# FLD_Logic_2.net
KiCad netlist of a schematic drawn in EAGLE
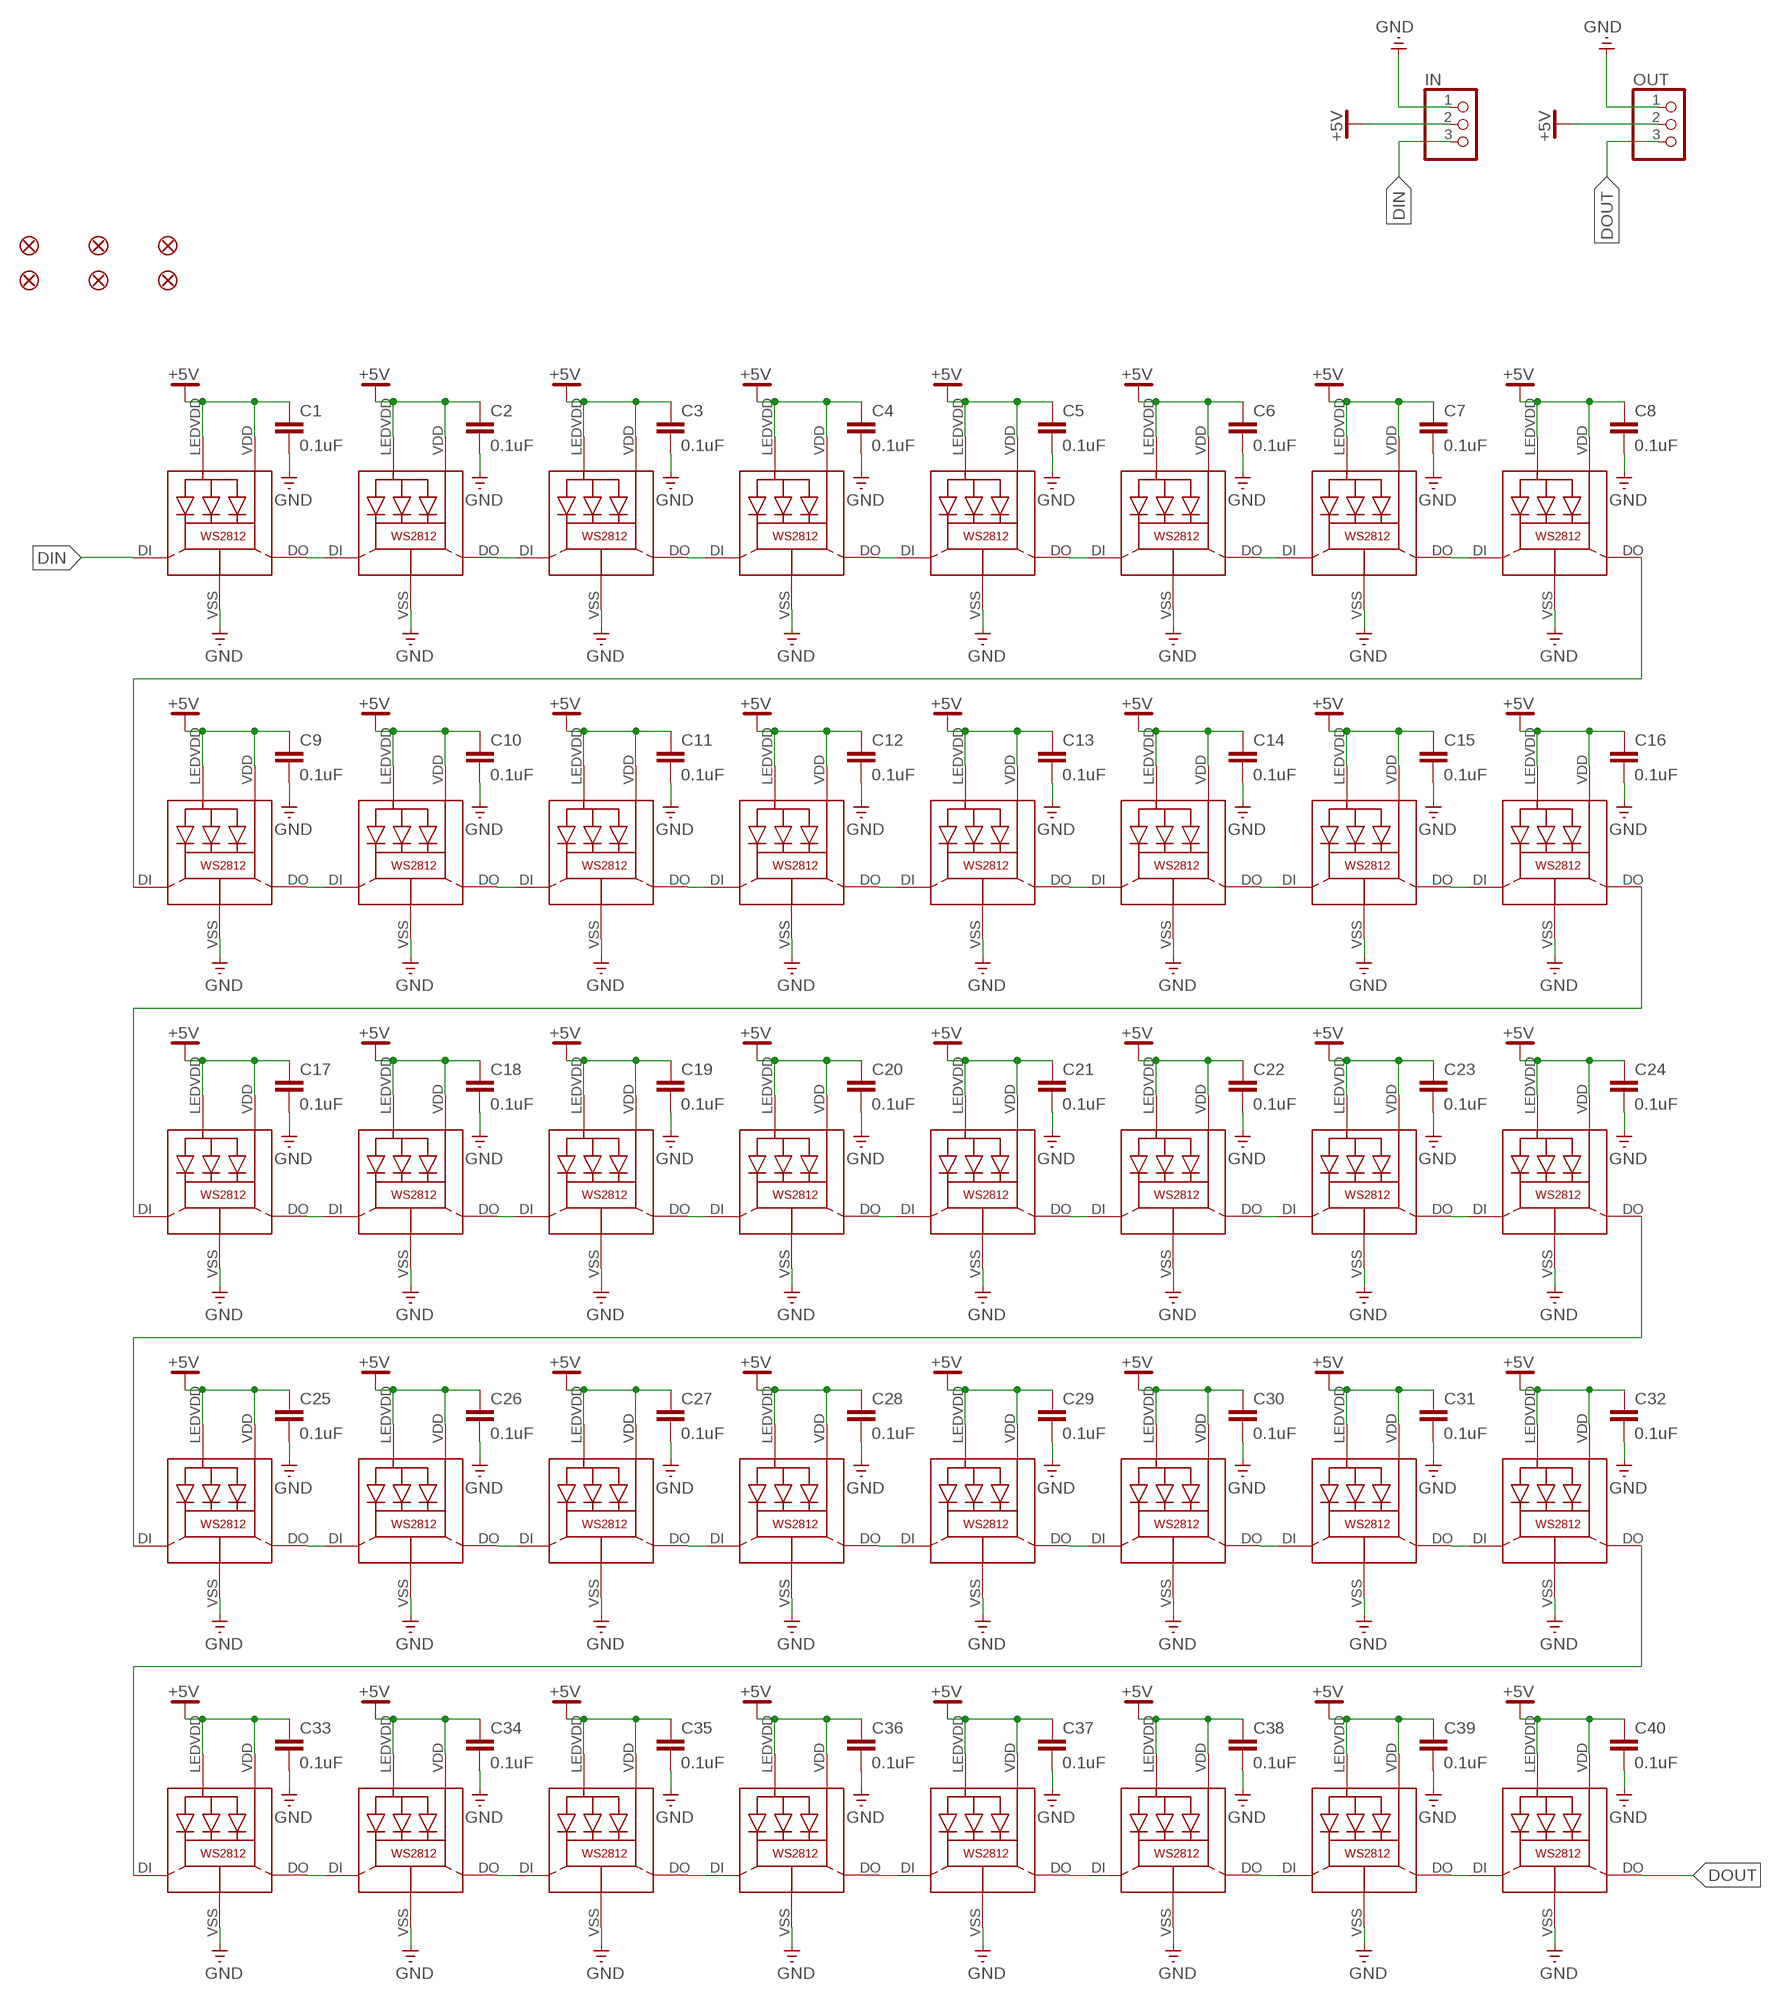
[diagram p0: schematic, sheet 1]

(export (version "E")
  (design (tool "Eeschema 10.0.6"))
  (components
    (comp (ref "C1")
      (value "0.1uF")
      (footprint "eagle-import:0805")
      (libsource (lib "eagle-import") (part "CAP0805"))
    )
    (comp (ref "C2")
      (value "0.1uF")
      (footprint "eagle-import:0805")
      (libsource (lib "eagle-import") (part "CAP0805"))
    )
    (comp (ref "C3")
      (value "0.1uF")
      (footprint "eagle-import:0805")
      (libsource (lib "eagle-import") (part "CAP0805"))
    )
    (comp (ref "C4")
      (value "0.1uF")
      (footprint "eagle-import:0805")
      (libsource (lib "eagle-import") (part "CAP0805"))
    )
    (comp (ref "C5")
      (value "0.1uF")
      (footprint "eagle-import:0805")
      (libsource (lib "eagle-import") (part "CAP0805"))
    )
    (comp (ref "C6")
      (value "0.1uF")
      (footprint "eagle-import:0805")
      (libsource (lib "eagle-import") (part "CAP0805"))
    )
    (comp (ref "C7")
      (value "0.1uF")
      (footprint "eagle-import:0805")
      (libsource (lib "eagle-import") (part "CAP0805"))
    )
    (comp (ref "C8")
      (value "0.1uF")
      (footprint "eagle-import:0805")
      (libsource (lib "eagle-import") (part "CAP0805"))
    )
    (comp (ref "C9")
      (value "0.1uF")
      (footprint "eagle-import:0805")
      (libsource (lib "eagle-import") (part "CAP0805"))
    )
    (comp (ref "C10")
      (value "0.1uF")
      (footprint "eagle-import:0805")
      (libsource (lib "eagle-import") (part "CAP0805"))
    )
    (comp (ref "C11")
      (value "0.1uF")
      (footprint "eagle-import:0805")
      (libsource (lib "eagle-import") (part "CAP0805"))
    )
    (comp (ref "C12")
      (value "0.1uF")
      (footprint "eagle-import:0805")
      (libsource (lib "eagle-import") (part "CAP0805"))
    )
    (comp (ref "C13")
      (value "0.1uF")
      (footprint "eagle-import:0805")
      (libsource (lib "eagle-import") (part "CAP0805"))
    )
    (comp (ref "C14")
      (value "0.1uF")
      (footprint "eagle-import:0805")
      (libsource (lib "eagle-import") (part "CAP0805"))
    )
    (comp (ref "C15")
      (value "0.1uF")
      (footprint "eagle-import:0805")
      (libsource (lib "eagle-import") (part "CAP0805"))
    )
    (comp (ref "C16")
      (value "0.1uF")
      (footprint "eagle-import:0805")
      (libsource (lib "eagle-import") (part "CAP0805"))
    )
    (comp (ref "C17")
      (value "0.1uF")
      (footprint "eagle-import:0805")
      (libsource (lib "eagle-import") (part "CAP0805"))
    )
    (comp (ref "C18")
      (value "0.1uF")
      (footprint "eagle-import:0805")
      (libsource (lib "eagle-import") (part "CAP0805"))
    )
    (comp (ref "C19")
      (value "0.1uF")
      (footprint "eagle-import:0805")
      (libsource (lib "eagle-import") (part "CAP0805"))
    )
    (comp (ref "C20")
      (value "0.1uF")
      (footprint "eagle-import:0805")
      (libsource (lib "eagle-import") (part "CAP0805"))
    )
    (comp (ref "C21")
      (value "0.1uF")
      (footprint "eagle-import:0805")
      (libsource (lib "eagle-import") (part "CAP0805"))
    )
    (comp (ref "C22")
      (value "0.1uF")
      (footprint "eagle-import:0805")
      (libsource (lib "eagle-import") (part "CAP0805"))
    )
    (comp (ref "C23")
      (value "0.1uF")
      (footprint "eagle-import:0805")
      (libsource (lib "eagle-import") (part "CAP0805"))
    )
    (comp (ref "C24")
      (value "0.1uF")
      (footprint "eagle-import:0805")
      (libsource (lib "eagle-import") (part "CAP0805"))
    )
    (comp (ref "C25")
      (value "0.1uF")
      (footprint "eagle-import:0805")
      (libsource (lib "eagle-import") (part "CAP0805"))
    )
    (comp (ref "C26")
      (value "0.1uF")
      (footprint "eagle-import:0805")
      (libsource (lib "eagle-import") (part "CAP0805"))
    )
    (comp (ref "C27")
      (value "0.1uF")
      (footprint "eagle-import:0805")
      (libsource (lib "eagle-import") (part "CAP0805"))
    )
    (comp (ref "C28")
      (value "0.1uF")
      (footprint "eagle-import:0805")
      (libsource (lib "eagle-import") (part "CAP0805"))
    )
    (comp (ref "C29")
      (value "0.1uF")
      (footprint "eagle-import:0805")
      (libsource (lib "eagle-import") (part "CAP0805"))
    )
    (comp (ref "C30")
      (value "0.1uF")
      (footprint "eagle-import:0805")
      (libsource (lib "eagle-import") (part "CAP0805"))
    )
    (comp (ref "C31")
      (value "0.1uF")
      (footprint "eagle-import:0805")
      (libsource (lib "eagle-import") (part "CAP0805"))
    )
    (comp (ref "C32")
      (value "0.1uF")
      (footprint "eagle-import:0805")
      (libsource (lib "eagle-import") (part "CAP0805"))
    )
    (comp (ref "C33")
      (value "0.1uF")
      (footprint "eagle-import:0805")
      (libsource (lib "eagle-import") (part "CAP0805"))
    )
    (comp (ref "C34")
      (value "0.1uF")
      (footprint "eagle-import:0805")
      (libsource (lib "eagle-import") (part "CAP0805"))
    )
    (comp (ref "C35")
      (value "0.1uF")
      (footprint "eagle-import:0805")
      (libsource (lib "eagle-import") (part "CAP0805"))
    )
    (comp (ref "C36")
      (value "0.1uF")
      (footprint "eagle-import:0805")
      (libsource (lib "eagle-import") (part "CAP0805"))
    )
    (comp (ref "C37")
      (value "0.1uF")
      (footprint "eagle-import:0805")
      (libsource (lib "eagle-import") (part "CAP0805"))
    )
    (comp (ref "C38")
      (value "0.1uF")
      (footprint "eagle-import:0805")
      (libsource (lib "eagle-import") (part "CAP0805"))
    )
    (comp (ref "C39")
      (value "0.1uF")
      (footprint "eagle-import:0805")
      (libsource (lib "eagle-import") (part "CAP0805"))
    )
    (comp (ref "C40")
      (value "0.1uF")
      (footprint "eagle-import:0805")
      (libsource (lib "eagle-import") (part "CAP0805"))
    )
    (comp (ref "FID1")
      (value "FIDUCIAL1.5X3")
      (footprint "eagle-import:FIDUCIAL-1.5X3")
      (libsource (lib "eagle-import") (part "FIDUCIAL1.5X3"))
    )
    (comp (ref "FID2")
      (value "FIDUCIAL1.5X3")
      (footprint "eagle-import:FIDUCIAL-1.5X3")
      (libsource (lib "eagle-import") (part "FIDUCIAL1.5X3"))
    )
    (comp (ref "FID3")
      (value "FIDUCIAL1.5X3")
      (footprint "eagle-import:FIDUCIAL-1.5X3")
      (libsource (lib "eagle-import") (part "FIDUCIAL1.5X3"))
    )
    (comp (ref "FID4")
      (value "FIDUCIAL1.5X3")
      (footprint "eagle-import:FIDUCIAL-1.5X3")
      (libsource (lib "eagle-import") (part "FIDUCIAL1.5X3"))
    )
    (comp (ref "FID5")
      (value "FIDUCIAL1.5X3")
      (footprint "eagle-import:FIDUCIAL-1.5X3")
      (libsource (lib "eagle-import") (part "FIDUCIAL1.5X3"))
    )
    (comp (ref "FID6")
      (value "FIDUCIAL1.5X3")
      (footprint "eagle-import:FIDUCIAL-1.5X3")
      (libsource (lib "eagle-import") (part "FIDUCIAL1.5X3"))
    )
    (comp (ref "IN")
      (value "PINHD-1X3")
      (footprint "eagle-import:1X03")
      (libsource (lib "eagle-import") (part "PINHD-1X3"))
    )
    (comp (ref "LED1")
      (value "WS2812")
      (footprint "eagle-import:WS2812")
      (libsource (lib "eagle-import") (part "WS2812"))
    )
    (comp (ref "LED2")
      (value "WS2812")
      (footprint "eagle-import:WS2812")
      (libsource (lib "eagle-import") (part "WS2812"))
    )
    (comp (ref "LED3")
      (value "WS2812")
      (footprint "eagle-import:WS2812")
      (libsource (lib "eagle-import") (part "WS2812"))
    )
    (comp (ref "LED4")
      (value "WS2812")
      (footprint "eagle-import:WS2812")
      (libsource (lib "eagle-import") (part "WS2812"))
    )
    (comp (ref "LED5")
      (value "WS2812")
      (footprint "eagle-import:WS2812")
      (libsource (lib "eagle-import") (part "WS2812"))
    )
    (comp (ref "LED6")
      (value "WS2812")
      (footprint "eagle-import:WS2812")
      (libsource (lib "eagle-import") (part "WS2812"))
    )
    (comp (ref "LED7")
      (value "WS2812")
      (footprint "eagle-import:WS2812")
      (libsource (lib "eagle-import") (part "WS2812"))
    )
    (comp (ref "LED8")
      (value "WS2812")
      (footprint "eagle-import:WS2812")
      (libsource (lib "eagle-import") (part "WS2812"))
    )
    (comp (ref "LED9")
      (value "WS2812")
      (footprint "eagle-import:WS2812")
      (libsource (lib "eagle-import") (part "WS2812"))
    )
    (comp (ref "LED10")
      (value "WS2812")
      (footprint "eagle-import:WS2812")
      (libsource (lib "eagle-import") (part "WS2812"))
    )
    (comp (ref "LED11")
      (value "WS2812")
      (footprint "eagle-import:WS2812")
      (libsource (lib "eagle-import") (part "WS2812"))
    )
    (comp (ref "LED12")
      (value "WS2812")
      (footprint "eagle-import:WS2812")
      (libsource (lib "eagle-import") (part "WS2812"))
    )
    (comp (ref "LED13")
      (value "WS2812")
      (footprint "eagle-import:WS2812")
      (libsource (lib "eagle-import") (part "WS2812"))
    )
    (comp (ref "LED14")
      (value "WS2812")
      (footprint "eagle-import:WS2812")
      (libsource (lib "eagle-import") (part "WS2812"))
    )
    (comp (ref "LED15")
      (value "WS2812")
      (footprint "eagle-import:WS2812")
      (libsource (lib "eagle-import") (part "WS2812"))
    )
    (comp (ref "LED16")
      (value "WS2812")
      (footprint "eagle-import:WS2812")
      (libsource (lib "eagle-import") (part "WS2812"))
    )
    (comp (ref "LED17")
      (value "WS2812")
      (footprint "eagle-import:WS2812")
      (libsource (lib "eagle-import") (part "WS2812"))
    )
    (comp (ref "LED18")
      (value "WS2812")
      (footprint "eagle-import:WS2812")
      (libsource (lib "eagle-import") (part "WS2812"))
    )
    (comp (ref "LED19")
      (value "WS2812")
      (footprint "eagle-import:WS2812")
      (libsource (lib "eagle-import") (part "WS2812"))
    )
    (comp (ref "LED20")
      (value "WS2812")
      (footprint "eagle-import:WS2812")
      (libsource (lib "eagle-import") (part "WS2812"))
    )
    (comp (ref "LED21")
      (value "WS2812")
      (footprint "eagle-import:WS2812")
      (libsource (lib "eagle-import") (part "WS2812"))
    )
    (comp (ref "LED22")
      (value "WS2812")
      (footprint "eagle-import:WS2812")
      (libsource (lib "eagle-import") (part "WS2812"))
    )
    (comp (ref "LED23")
      (value "WS2812")
      (footprint "eagle-import:WS2812")
      (libsource (lib "eagle-import") (part "WS2812"))
    )
    (comp (ref "LED24")
      (value "WS2812")
      (footprint "eagle-import:WS2812")
      (libsource (lib "eagle-import") (part "WS2812"))
    )
    (comp (ref "LED25")
      (value "WS2812")
      (footprint "eagle-import:WS2812")
      (libsource (lib "eagle-import") (part "WS2812"))
    )
    (comp (ref "LED26")
      (value "WS2812")
      (footprint "eagle-import:WS2812")
      (libsource (lib "eagle-import") (part "WS2812"))
    )
    (comp (ref "LED27")
      (value "WS2812")
      (footprint "eagle-import:WS2812")
      (libsource (lib "eagle-import") (part "WS2812"))
    )
    (comp (ref "LED28")
      (value "WS2812")
      (footprint "eagle-import:WS2812")
      (libsource (lib "eagle-import") (part "WS2812"))
    )
    (comp (ref "LED29")
      (value "WS2812")
      (footprint "eagle-import:WS2812")
      (libsource (lib "eagle-import") (part "WS2812"))
    )
    (comp (ref "LED30")
      (value "WS2812")
      (footprint "eagle-import:WS2812")
      (libsource (lib "eagle-import") (part "WS2812"))
    )
    (comp (ref "LED31")
      (value "WS2812")
      (footprint "eagle-import:WS2812")
      (libsource (lib "eagle-import") (part "WS2812"))
    )
    (comp (ref "LED32")
      (value "WS2812")
      (footprint "eagle-import:WS2812")
      (libsource (lib "eagle-import") (part "WS2812"))
    )
    (comp (ref "LED33")
      (value "WS2812")
      (footprint "eagle-import:WS2812")
      (libsource (lib "eagle-import") (part "WS2812"))
    )
    (comp (ref "LED34")
      (value "WS2812")
      (footprint "eagle-import:WS2812")
      (libsource (lib "eagle-import") (part "WS2812"))
    )
    (comp (ref "LED35")
      (value "WS2812")
      (footprint "eagle-import:WS2812")
      (libsource (lib "eagle-import") (part "WS2812"))
    )
    (comp (ref "LED36")
      (value "WS2812")
      (footprint "eagle-import:WS2812")
      (libsource (lib "eagle-import") (part "WS2812"))
    )
    (comp (ref "LED37")
      (value "WS2812")
      (footprint "eagle-import:WS2812")
      (libsource (lib "eagle-import") (part "WS2812"))
    )
    (comp (ref "LED38")
      (value "WS2812")
      (footprint "eagle-import:WS2812")
      (libsource (lib "eagle-import") (part "WS2812"))
    )
    (comp (ref "LED39")
      (value "WS2812")
      (footprint "eagle-import:WS2812")
      (libsource (lib "eagle-import") (part "WS2812"))
    )
    (comp (ref "LED40")
      (value "WS2812")
      (footprint "eagle-import:WS2812")
      (libsource (lib "eagle-import") (part "WS2812"))
    )
    (comp (ref "OUT")
      (value "PINHD-1X3")
      (footprint "eagle-import:1X03")
      (libsource (lib "eagle-import") (part "PINHD-1X3"))
    )
  )
  (nets
    (net (code "1") (name "+5V") (class "Default")
      (node (ref "C1") (pin "1") (pinfunction "1_1") (pintype "passive"))
      (node (ref "C10") (pin "1") (pinfunction "1_1") (pintype "passive"))
      (node (ref "C11") (pin "1") (pinfunction "1_1") (pintype "passive"))
      (node (ref "C12") (pin "1") (pinfunction "1_1") (pintype "passive"))
      (node (ref "C13") (pin "1") (pinfunction "1_1") (pintype "passive"))
      (node (ref "C14") (pin "1") (pinfunction "1_1") (pintype "passive"))
      (node (ref "C15") (pin "1") (pinfunction "1_1") (pintype "passive"))
      (node (ref "C16") (pin "1") (pinfunction "1_1") (pintype "passive"))
      (node (ref "C17") (pin "1") (pinfunction "1_1") (pintype "passive"))
      (node (ref "C18") (pin "1") (pinfunction "1_1") (pintype "passive"))
      (node (ref "C19") (pin "1") (pinfunction "1_1") (pintype "passive"))
      (node (ref "C2") (pin "1") (pinfunction "1_1") (pintype "passive"))
      (node (ref "C20") (pin "1") (pinfunction "1_1") (pintype "passive"))
      (node (ref "C21") (pin "1") (pinfunction "1_1") (pintype "passive"))
      (node (ref "C22") (pin "1") (pinfunction "1_1") (pintype "passive"))
      (node (ref "C23") (pin "1") (pinfunction "1_1") (pintype "passive"))
      (node (ref "C24") (pin "1") (pinfunction "1_1") (pintype "passive"))
      (node (ref "C25") (pin "1") (pinfunction "1_1") (pintype "passive"))
      (node (ref "C26") (pin "1") (pinfunction "1_1") (pintype "passive"))
      (node (ref "C27") (pin "1") (pinfunction "1_1") (pintype "passive"))
      (node (ref "C28") (pin "1") (pinfunction "1_1") (pintype "passive"))
      (node (ref "C29") (pin "1") (pinfunction "1_1") (pintype "passive"))
      (node (ref "C3") (pin "1") (pinfunction "1_1") (pintype "passive"))
      (node (ref "C30") (pin "1") (pinfunction "1_1") (pintype "passive"))
      (node (ref "C31") (pin "1") (pinfunction "1_1") (pintype "passive"))
      (node (ref "C32") (pin "1") (pinfunction "1_1") (pintype "passive"))
      (node (ref "C33") (pin "1") (pinfunction "1_1") (pintype "passive"))
      (node (ref "C34") (pin "1") (pinfunction "1_1") (pintype "passive"))
      (node (ref "C35") (pin "1") (pinfunction "1_1") (pintype "passive"))
      (node (ref "C36") (pin "1") (pinfunction "1_1") (pintype "passive"))
      (node (ref "C37") (pin "1") (pinfunction "1_1") (pintype "passive"))
      (node (ref "C38") (pin "1") (pinfunction "1_1") (pintype "passive"))
      (node (ref "C39") (pin "1") (pinfunction "1_1") (pintype "passive"))
      (node (ref "C4") (pin "1") (pinfunction "1_1") (pintype "passive"))
      (node (ref "C40") (pin "1") (pinfunction "1_1") (pintype "passive"))
      (node (ref "C5") (pin "1") (pinfunction "1_1") (pintype "passive"))
      (node (ref "C6") (pin "1") (pinfunction "1_1") (pintype "passive"))
      (node (ref "C7") (pin "1") (pinfunction "1_1") (pintype "passive"))
      (node (ref "C8") (pin "1") (pinfunction "1_1") (pintype "passive"))
      (node (ref "C9") (pin "1") (pinfunction "1_1") (pintype "passive"))
      (node (ref "IN") (pin "2") (pinfunction "2_2") (pintype "passive"))
      (node (ref "LED1") (pin "LEDVDD") (pinfunction "LEDVDD_LEDVDD") (pintype "power_in"))
      (node (ref "LED1") (pin "VDD") (pinfunction "VDD_VDD") (pintype "power_in"))
      (node (ref "LED10") (pin "LEDVDD") (pinfunction "LEDVDD_LEDVDD") (pintype "power_in"))
      (node (ref "LED10") (pin "VDD") (pinfunction "VDD_VDD") (pintype "power_in"))
      (node (ref "LED11") (pin "LEDVDD") (pinfunction "LEDVDD_LEDVDD") (pintype "power_in"))
      (node (ref "LED11") (pin "VDD") (pinfunction "VDD_VDD") (pintype "power_in"))
      (node (ref "LED12") (pin "LEDVDD") (pinfunction "LEDVDD_LEDVDD") (pintype "power_in"))
      (node (ref "LED12") (pin "VDD") (pinfunction "VDD_VDD") (pintype "power_in"))
      (node (ref "LED13") (pin "LEDVDD") (pinfunction "LEDVDD_LEDVDD") (pintype "power_in"))
      (node (ref "LED13") (pin "VDD") (pinfunction "VDD_VDD") (pintype "power_in"))
      (node (ref "LED14") (pin "LEDVDD") (pinfunction "LEDVDD_LEDVDD") (pintype "power_in"))
      (node (ref "LED14") (pin "VDD") (pinfunction "VDD_VDD") (pintype "power_in"))
      (node (ref "LED15") (pin "LEDVDD") (pinfunction "LEDVDD_LEDVDD") (pintype "power_in"))
      (node (ref "LED15") (pin "VDD") (pinfunction "VDD_VDD") (pintype "power_in"))
      (node (ref "LED16") (pin "LEDVDD") (pinfunction "LEDVDD_LEDVDD") (pintype "power_in"))
      (node (ref "LED16") (pin "VDD") (pinfunction "VDD_VDD") (pintype "power_in"))
      (node (ref "LED17") (pin "LEDVDD") (pinfunction "LEDVDD_LEDVDD") (pintype "power_in"))
      (node (ref "LED17") (pin "VDD") (pinfunction "VDD_VDD") (pintype "power_in"))
      (node (ref "LED18") (pin "LEDVDD") (pinfunction "LEDVDD_LEDVDD") (pintype "power_in"))
      (node (ref "LED18") (pin "VDD") (pinfunction "VDD_VDD") (pintype "power_in"))
      (node (ref "LED19") (pin "LEDVDD") (pinfunction "LEDVDD_LEDVDD") (pintype "power_in"))
      (node (ref "LED19") (pin "VDD") (pinfunction "VDD_VDD") (pintype "power_in"))
      (node (ref "LED2") (pin "LEDVDD") (pinfunction "LEDVDD_LEDVDD") (pintype "power_in"))
      (node (ref "LED2") (pin "VDD") (pinfunction "VDD_VDD") (pintype "power_in"))
      (node (ref "LED20") (pin "LEDVDD") (pinfunction "LEDVDD_LEDVDD") (pintype "power_in"))
      (node (ref "LED20") (pin "VDD") (pinfunction "VDD_VDD") (pintype "power_in"))
      (node (ref "LED21") (pin "LEDVDD") (pinfunction "LEDVDD_LEDVDD") (pintype "power_in"))
      (node (ref "LED21") (pin "VDD") (pinfunction "VDD_VDD") (pintype "power_in"))
      (node (ref "LED22") (pin "LEDVDD") (pinfunction "LEDVDD_LEDVDD") (pintype "power_in"))
      (node (ref "LED22") (pin "VDD") (pinfunction "VDD_VDD") (pintype "power_in"))
      (node (ref "LED23") (pin "LEDVDD") (pinfunction "LEDVDD_LEDVDD") (pintype "power_in"))
      (node (ref "LED23") (pin "VDD") (pinfunction "VDD_VDD") (pintype "power_in"))
      (node (ref "LED24") (pin "LEDVDD") (pinfunction "LEDVDD_LEDVDD") (pintype "power_in"))
      (node (ref "LED24") (pin "VDD") (pinfunction "VDD_VDD") (pintype "power_in"))
      (node (ref "LED25") (pin "LEDVDD") (pinfunction "LEDVDD_LEDVDD") (pintype "power_in"))
      (node (ref "LED25") (pin "VDD") (pinfunction "VDD_VDD") (pintype "power_in"))
      (node (ref "LED26") (pin "LEDVDD") (pinfunction "LEDVDD_LEDVDD") (pintype "power_in"))
      (node (ref "LED26") (pin "VDD") (pinfunction "VDD_VDD") (pintype "power_in"))
      (node (ref "LED27") (pin "LEDVDD") (pinfunction "LEDVDD_LEDVDD") (pintype "power_in"))
      (node (ref "LED27") (pin "VDD") (pinfunction "VDD_VDD") (pintype "power_in"))
      (node (ref "LED28") (pin "LEDVDD") (pinfunction "LEDVDD_LEDVDD") (pintype "power_in"))
      (node (ref "LED28") (pin "VDD") (pinfunction "VDD_VDD") (pintype "power_in"))
      (node (ref "LED29") (pin "LEDVDD") (pinfunction "LEDVDD_LEDVDD") (pintype "power_in"))
      (node (ref "LED29") (pin "VDD") (pinfunction "VDD_VDD") (pintype "power_in"))
      (node (ref "LED3") (pin "LEDVDD") (pinfunction "LEDVDD_LEDVDD") (pintype "power_in"))
      (node (ref "LED3") (pin "VDD") (pinfunction "VDD_VDD") (pintype "power_in"))
      (node (ref "LED30") (pin "LEDVDD") (pinfunction "LEDVDD_LEDVDD") (pintype "power_in"))
      (node (ref "LED30") (pin "VDD") (pinfunction "VDD_VDD") (pintype "power_in"))
      (node (ref "LED31") (pin "LEDVDD") (pinfunction "LEDVDD_LEDVDD") (pintype "power_in"))
      (node (ref "LED31") (pin "VDD") (pinfunction "VDD_VDD") (pintype "power_in"))
      (node (ref "LED32") (pin "LEDVDD") (pinfunction "LEDVDD_LEDVDD") (pintype "power_in"))
      (node (ref "LED32") (pin "VDD") (pinfunction "VDD_VDD") (pintype "power_in"))
      (node (ref "LED33") (pin "LEDVDD") (pinfunction "LEDVDD_LEDVDD") (pintype "power_in"))
      (node (ref "LED33") (pin "VDD") (pinfunction "VDD_VDD") (pintype "power_in"))
      (node (ref "LED34") (pin "LEDVDD") (pinfunction "LEDVDD_LEDVDD") (pintype "power_in"))
      (node (ref "LED34") (pin "VDD") (pinfunction "VDD_VDD") (pintype "power_in"))
      (node (ref "LED35") (pin "LEDVDD") (pinfunction "LEDVDD_LEDVDD") (pintype "power_in"))
      (node (ref "LED35") (pin "VDD") (pinfunction "VDD_VDD") (pintype "power_in"))
      (node (ref "LED36") (pin "LEDVDD") (pinfunction "LEDVDD_LEDVDD") (pintype "power_in"))
      (node (ref "LED36") (pin "VDD") (pinfunction "VDD_VDD") (pintype "power_in"))
      (node (ref "LED37") (pin "LEDVDD") (pinfunction "LEDVDD_LEDVDD") (pintype "power_in"))
      (node (ref "LED37") (pin "VDD") (pinfunction "VDD_VDD") (pintype "power_in"))
      (node (ref "LED38") (pin "LEDVDD") (pinfunction "LEDVDD_LEDVDD") (pintype "power_in"))
      (node (ref "LED38") (pin "VDD") (pinfunction "VDD_VDD") (pintype "power_in"))
      (node (ref "LED39") (pin "LEDVDD") (pinfunction "LEDVDD_LEDVDD") (pintype "power_in"))
      (node (ref "LED39") (pin "VDD") (pinfunction "VDD_VDD") (pintype "power_in"))
      (node (ref "LED4") (pin "LEDVDD") (pinfunction "LEDVDD_LEDVDD") (pintype "power_in"))
      (node (ref "LED4") (pin "VDD") (pinfunction "VDD_VDD") (pintype "power_in"))
      (node (ref "LED40") (pin "LEDVDD") (pinfunction "LEDVDD_LEDVDD") (pintype "power_in"))
      (node (ref "LED40") (pin "VDD") (pinfunction "VDD_VDD") (pintype "power_in"))
      (node (ref "LED5") (pin "LEDVDD") (pinfunction "LEDVDD_LEDVDD") (pintype "power_in"))
      (node (ref "LED5") (pin "VDD") (pinfunction "VDD_VDD") (pintype "power_in"))
      (node (ref "LED6") (pin "LEDVDD") (pinfunction "LEDVDD_LEDVDD") (pintype "power_in"))
      (node (ref "LED6") (pin "VDD") (pinfunction "VDD_VDD") (pintype "power_in"))
      (node (ref "LED7") (pin "LEDVDD") (pinfunction "LEDVDD_LEDVDD") (pintype "power_in"))
      (node (ref "LED7") (pin "VDD") (pinfunction "VDD_VDD") (pintype "power_in"))
      (node (ref "LED8") (pin "LEDVDD") (pinfunction "LEDVDD_LEDVDD") (pintype "power_in"))
      (node (ref "LED8") (pin "VDD") (pinfunction "VDD_VDD") (pintype "power_in"))
      (node (ref "LED9") (pin "LEDVDD") (pinfunction "LEDVDD_LEDVDD") (pintype "power_in"))
      (node (ref "LED9") (pin "VDD") (pinfunction "VDD_VDD") (pintype "power_in"))
      (node (ref "OUT") (pin "2") (pinfunction "2_2") (pintype "passive"))
    )
    (net (code "2") (name "DIN") (class "Default")
      (node (ref "IN") (pin "3") (pinfunction "3_3") (pintype "passive"))
      (node (ref "LED1") (pin "DI") (pinfunction "DI_DI") (pintype "input"))
    )
    (net (code "3") (name "DOUT") (class "Default")
      (node (ref "LED40") (pin "DO") (pinfunction "DO_DO") (pintype "output"))
      (node (ref "OUT") (pin "3") (pinfunction "3_3") (pintype "passive"))
    )
    (net (code "4") (name "GND") (class "Default")
      (node (ref "C1") (pin "2") (pinfunction "2_2") (pintype "passive"))
      (node (ref "C10") (pin "2") (pinfunction "2_2") (pintype "passive"))
      (node (ref "C11") (pin "2") (pinfunction "2_2") (pintype "passive"))
      (node (ref "C12") (pin "2") (pinfunction "2_2") (pintype "passive"))
      (node (ref "C13") (pin "2") (pinfunction "2_2") (pintype "passive"))
      (node (ref "C14") (pin "2") (pinfunction "2_2") (pintype "passive"))
      (node (ref "C15") (pin "2") (pinfunction "2_2") (pintype "passive"))
      (node (ref "C16") (pin "2") (pinfunction "2_2") (pintype "passive"))
      (node (ref "C17") (pin "2") (pinfunction "2_2") (pintype "passive"))
      (node (ref "C18") (pin "2") (pinfunction "2_2") (pintype "passive"))
      (node (ref "C19") (pin "2") (pinfunction "2_2") (pintype "passive"))
      (node (ref "C2") (pin "2") (pinfunction "2_2") (pintype "passive"))
      (node (ref "C20") (pin "2") (pinfunction "2_2") (pintype "passive"))
      (node (ref "C21") (pin "2") (pinfunction "2_2") (pintype "passive"))
      (node (ref "C22") (pin "2") (pinfunction "2_2") (pintype "passive"))
      (node (ref "C23") (pin "2") (pinfunction "2_2") (pintype "passive"))
      (node (ref "C24") (pin "2") (pinfunction "2_2") (pintype "passive"))
      (node (ref "C25") (pin "2") (pinfunction "2_2") (pintype "passive"))
      (node (ref "C26") (pin "2") (pinfunction "2_2") (pintype "passive"))
      (node (ref "C27") (pin "2") (pinfunction "2_2") (pintype "passive"))
      (node (ref "C28") (pin "2") (pinfunction "2_2") (pintype "passive"))
      (node (ref "C29") (pin "2") (pinfunction "2_2") (pintype "passive"))
      (node (ref "C3") (pin "2") (pinfunction "2_2") (pintype "passive"))
      (node (ref "C30") (pin "2") (pinfunction "2_2") (pintype "passive"))
      (node (ref "C31") (pin "2") (pinfunction "2_2") (pintype "passive"))
      (node (ref "C32") (pin "2") (pinfunction "2_2") (pintype "passive"))
      (node (ref "C33") (pin "2") (pinfunction "2_2") (pintype "passive"))
      (node (ref "C34") (pin "2") (pinfunction "2_2") (pintype "passive"))
      (node (ref "C35") (pin "2") (pinfunction "2_2") (pintype "passive"))
      (node (ref "C36") (pin "2") (pinfunction "2_2") (pintype "passive"))
      (node (ref "C37") (pin "2") (pinfunction "2_2") (pintype "passive"))
      (node (ref "C38") (pin "2") (pinfunction "2_2") (pintype "passive"))
      (node (ref "C39") (pin "2") (pinfunction "2_2") (pintype "passive"))
      (node (ref "C4") (pin "2") (pinfunction "2_2") (pintype "passive"))
      (node (ref "C40") (pin "2") (pinfunction "2_2") (pintype "passive"))
      (node (ref "C5") (pin "2") (pinfunction "2_2") (pintype "passive"))
      (node (ref "C6") (pin "2") (pinfunction "2_2") (pintype "passive"))
      (node (ref "C7") (pin "2") (pinfunction "2_2") (pintype "passive"))
      (node (ref "C8") (pin "2") (pinfunction "2_2") (pintype "passive"))
      (node (ref "C9") (pin "2") (pinfunction "2_2") (pintype "passive"))
      (node (ref "IN") (pin "1") (pinfunction "1_1") (pintype "passive"))
      (node (ref "LED1") (pin "VSS") (pinfunction "GND_VSS") (pintype "power_in"))
      (node (ref "LED10") (pin "VSS") (pinfunction "GND_VSS") (pintype "power_in"))
      (node (ref "LED11") (pin "VSS") (pinfunction "GND_VSS") (pintype "power_in"))
      (node (ref "LED12") (pin "VSS") (pinfunction "GND_VSS") (pintype "power_in"))
      (node (ref "LED13") (pin "VSS") (pinfunction "GND_VSS") (pintype "power_in"))
      (node (ref "LED14") (pin "VSS") (pinfunction "GND_VSS") (pintype "power_in"))
      (node (ref "LED15") (pin "VSS") (pinfunction "GND_VSS") (pintype "power_in"))
      (node (ref "LED16") (pin "VSS") (pinfunction "GND_VSS") (pintype "power_in"))
      (node (ref "LED17") (pin "VSS") (pinfunction "GND_VSS") (pintype "power_in"))
      (node (ref "LED18") (pin "VSS") (pinfunction "GND_VSS") (pintype "power_in"))
      (node (ref "LED19") (pin "VSS") (pinfunction "GND_VSS") (pintype "power_in"))
      (node (ref "LED2") (pin "VSS") (pinfunction "GND_VSS") (pintype "power_in"))
      (node (ref "LED20") (pin "VSS") (pinfunction "GND_VSS") (pintype "power_in"))
      (node (ref "LED21") (pin "VSS") (pinfunction "GND_VSS") (pintype "power_in"))
      (node (ref "LED22") (pin "VSS") (pinfunction "GND_VSS") (pintype "power_in"))
      (node (ref "LED23") (pin "VSS") (pinfunction "GND_VSS") (pintype "power_in"))
      (node (ref "LED24") (pin "VSS") (pinfunction "GND_VSS") (pintype "power_in"))
      (node (ref "LED25") (pin "VSS") (pinfunction "GND_VSS") (pintype "power_in"))
      (node (ref "LED26") (pin "VSS") (pinfunction "GND_VSS") (pintype "power_in"))
      (node (ref "LED27") (pin "VSS") (pinfunction "GND_VSS") (pintype "power_in"))
      (node (ref "LED28") (pin "VSS") (pinfunction "GND_VSS") (pintype "power_in"))
      (node (ref "LED29") (pin "VSS") (pinfunction "GND_VSS") (pintype "power_in"))
      (node (ref "LED3") (pin "VSS") (pinfunction "GND_VSS") (pintype "power_in"))
      (node (ref "LED30") (pin "VSS") (pinfunction "GND_VSS") (pintype "power_in"))
      (node (ref "LED31") (pin "VSS") (pinfunction "GND_VSS") (pintype "power_in"))
      (node (ref "LED32") (pin "VSS") (pinfunction "GND_VSS") (pintype "power_in"))
      (node (ref "LED33") (pin "VSS") (pinfunction "GND_VSS") (pintype "power_in"))
      (node (ref "LED34") (pin "VSS") (pinfunction "GND_VSS") (pintype "power_in"))
      (node (ref "LED35") (pin "VSS") (pinfunction "GND_VSS") (pintype "power_in"))
      (node (ref "LED36") (pin "VSS") (pinfunction "GND_VSS") (pintype "power_in"))
      (node (ref "LED37") (pin "VSS") (pinfunction "GND_VSS") (pintype "power_in"))
      (node (ref "LED38") (pin "VSS") (pinfunction "GND_VSS") (pintype "power_in"))
      (node (ref "LED39") (pin "VSS") (pinfunction "GND_VSS") (pintype "power_in"))
      (node (ref "LED4") (pin "VSS") (pinfunction "GND_VSS") (pintype "power_in"))
      (node (ref "LED40") (pin "VSS") (pinfunction "GND_VSS") (pintype "power_in"))
      (node (ref "LED5") (pin "VSS") (pinfunction "GND_VSS") (pintype "power_in"))
      (node (ref "LED6") (pin "VSS") (pinfunction "GND_VSS") (pintype "power_in"))
      (node (ref "LED7") (pin "VSS") (pinfunction "GND_VSS") (pintype "power_in"))
      (node (ref "LED8") (pin "VSS") (pinfunction "GND_VSS") (pintype "power_in"))
      (node (ref "LED9") (pin "VSS") (pinfunction "GND_VSS") (pintype "power_in"))
      (node (ref "OUT") (pin "1") (pinfunction "1_1") (pintype "passive"))
    )
    (net (code "5") (name "Net-(LED1-PadDO)") (class "Default")
      (node (ref "LED1") (pin "DO") (pinfunction "DO_DO") (pintype "output"))
      (node (ref "LED2") (pin "DI") (pinfunction "DI_DI") (pintype "input"))
    )
    (net (code "6") (name "Net-(LED2-PadDO)") (class "Default")
      (node (ref "LED2") (pin "DO") (pinfunction "DO_DO") (pintype "output"))
      (node (ref "LED3") (pin "DI") (pinfunction "DI_DI") (pintype "input"))
    )
    (net (code "7") (name "Net-(LED3-PadDO)") (class "Default")
      (node (ref "LED3") (pin "DO") (pinfunction "DO_DO") (pintype "output"))
      (node (ref "LED4") (pin "DI") (pinfunction "DI_DI") (pintype "input"))
    )
    (net (code "8") (name "Net-(LED4-PadDO)") (class "Default")
      (node (ref "LED4") (pin "DO") (pinfunction "DO_DO") (pintype "output"))
      (node (ref "LED5") (pin "DI") (pinfunction "DI_DI") (pintype "input"))
    )
    (net (code "9") (name "Net-(LED5-PadDO)") (class "Default")
      (node (ref "LED5") (pin "DO") (pinfunction "DO_DO") (pintype "output"))
      (node (ref "LED6") (pin "DI") (pinfunction "DI_DI") (pintype "input"))
    )
    (net (code "10") (name "Net-(LED6-PadDO)") (class "Default")
      (node (ref "LED6") (pin "DO") (pinfunction "DO_DO") (pintype "output"))
      (node (ref "LED7") (pin "DI") (pinfunction "DI_DI") (pintype "input"))
    )
    (net (code "11") (name "Net-(LED7-PadDO)") (class "Default")
      (node (ref "LED7") (pin "DO") (pinfunction "DO_DO") (pintype "output"))
      (node (ref "LED8") (pin "DI") (pinfunction "DI_DI") (pintype "input"))
    )
    (net (code "12") (name "Net-(LED8-PadDO)") (class "Default")
      (node (ref "LED8") (pin "DO") (pinfunction "DO_DO") (pintype "output"))
      (node (ref "LED9") (pin "DI") (pinfunction "DI_DI") (pintype "input"))
    )
    (net (code "13") (name "Net-(LED10-PadDI)") (class "Default")
      (node (ref "LED10") (pin "DI") (pinfunction "DI_DI") (pintype "input"))
      (node (ref "LED9") (pin "DO") (pinfunction "DO_DO") (pintype "output"))
    )
    (net (code "14") (name "Net-(LED10-PadDO)") (class "Default")
      (node (ref "LED10") (pin "DO") (pinfunction "DO_DO") (pintype "output"))
      (node (ref "LED11") (pin "DI") (pinfunction "DI_DI") (pintype "input"))
    )
    (net (code "15") (name "Net-(LED11-PadDO)") (class "Default")
      (node (ref "LED11") (pin "DO") (pinfunction "DO_DO") (pintype "output"))
      (node (ref "LED12") (pin "DI") (pinfunction "DI_DI") (pintype "input"))
    )
    (net (code "16") (name "Net-(LED12-PadDO)") (class "Default")
      (node (ref "LED12") (pin "DO") (pinfunction "DO_DO") (pintype "output"))
      (node (ref "LED13") (pin "DI") (pinfunction "DI_DI") (pintype "input"))
    )
    (net (code "17") (name "Net-(LED13-PadDO)") (class "Default")
      (node (ref "LED13") (pin "DO") (pinfunction "DO_DO") (pintype "output"))
      (node (ref "LED14") (pin "DI") (pinfunction "DI_DI") (pintype "input"))
    )
    (net (code "18") (name "Net-(LED14-PadDO)") (class "Default")
      (node (ref "LED14") (pin "DO") (pinfunction "DO_DO") (pintype "output"))
      (node (ref "LED15") (pin "DI") (pinfunction "DI_DI") (pintype "input"))
    )
    (net (code "19") (name "Net-(LED15-PadDO)") (class "Default")
      (node (ref "LED15") (pin "DO") (pinfunction "DO_DO") (pintype "output"))
      (node (ref "LED16") (pin "DI") (pinfunction "DI_DI") (pintype "input"))
    )
    (net (code "20") (name "Net-(LED16-PadDO)") (class "Default")
      (node (ref "LED16") (pin "DO") (pinfunction "DO_DO") (pintype "output"))
      (node (ref "LED17") (pin "DI") (pinfunction "DI_DI") (pintype "input"))
    )
    (net (code "21") (name "Net-(LED17-PadDO)") (class "Default")
      (node (ref "LED17") (pin "DO") (pinfunction "DO_DO") (pintype "output"))
      (node (ref "LED18") (pin "DI") (pinfunction "DI_DI") (pintype "input"))
    )
    (net (code "22") (name "Net-(LED18-PadDO)") (class "Default")
      (node (ref "LED18") (pin "DO") (pinfunction "DO_DO") (pintype "output"))
      (node (ref "LED19") (pin "DI") (pinfunction "DI_DI") (pintype "input"))
    )
    (net (code "23") (name "Net-(LED19-PadDO)") (class "Default")
      (node (ref "LED19") (pin "DO") (pinfunction "DO_DO") (pintype "output"))
      (node (ref "LED20") (pin "DI") (pinfunction "DI_DI") (pintype "input"))
    )
    (net (code "24") (name "Net-(LED20-PadDO)") (class "Default")
      (node (ref "LED20") (pin "DO") (pinfunction "DO_DO") (pintype "output"))
      (node (ref "LED21") (pin "DI") (pinfunction "DI_DI") (pintype "input"))
    )
    (net (code "25") (name "Net-(LED21-PadDO)") (class "Default")
      (node (ref "LED21") (pin "DO") (pinfunction "DO_DO") (pintype "output"))
      (node (ref "LED22") (pin "DI") (pinfunction "DI_DI") (pintype "input"))
    )
    (net (code "26") (name "Net-(LED22-PadDO)") (class "Default")
      (node (ref "LED22") (pin "DO") (pinfunction "DO_DO") (pintype "output"))
      (node (ref "LED23") (pin "DI") (pinfunction "DI_DI") (pintype "input"))
    )
    (net (code "27") (name "Net-(LED23-PadDO)") (class "Default")
      (node (ref "LED23") (pin "DO") (pinfunction "DO_DO") (pintype "output"))
      (node (ref "LED24") (pin "DI") (pinfunction "DI_DI") (pintype "input"))
    )
    (net (code "28") (name "Net-(LED24-PadDO)") (class "Default")
      (node (ref "LED24") (pin "DO") (pinfunction "DO_DO") (pintype "output"))
      (node (ref "LED25") (pin "DI") (pinfunction "DI_DI") (pintype "input"))
    )
    (net (code "29") (name "Net-(LED25-PadDO)") (class "Default")
      (node (ref "LED25") (pin "DO") (pinfunction "DO_DO") (pintype "output"))
      (node (ref "LED26") (pin "DI") (pinfunction "DI_DI") (pintype "input"))
    )
    (net (code "30") (name "Net-(LED26-PadDO)") (class "Default")
      (node (ref "LED26") (pin "DO") (pinfunction "DO_DO") (pintype "output"))
      (node (ref "LED27") (pin "DI") (pinfunction "DI_DI") (pintype "input"))
    )
    (net (code "31") (name "Net-(LED27-PadDO)") (class "Default")
      (node (ref "LED27") (pin "DO") (pinfunction "DO_DO") (pintype "output"))
      (node (ref "LED28") (pin "DI") (pinfunction "DI_DI") (pintype "input"))
    )
    (net (code "32") (name "Net-(LED28-PadDO)") (class "Default")
      (node (ref "LED28") (pin "DO") (pinfunction "DO_DO") (pintype "output"))
      (node (ref "LED29") (pin "DI") (pinfunction "DI_DI") (pintype "input"))
    )
    (net (code "33") (name "Net-(LED29-PadDO)") (class "Default")
      (node (ref "LED29") (pin "DO") (pinfunction "DO_DO") (pintype "output"))
      (node (ref "LED30") (pin "DI") (pinfunction "DI_DI") (pintype "input"))
    )
    (net (code "34") (name "Net-(LED30-PadDO)") (class "Default")
      (node (ref "LED30") (pin "DO") (pinfunction "DO_DO") (pintype "output"))
      (node (ref "LED31") (pin "DI") (pinfunction "DI_DI") (pintype "input"))
    )
    (net (code "35") (name "Net-(LED31-PadDO)") (class "Default")
      (node (ref "LED31") (pin "DO") (pinfunction "DO_DO") (pintype "output"))
      (node (ref "LED32") (pin "DI") (pinfunction "DI_DI") (pintype "input"))
    )
    (net (code "36") (name "Net-(LED32-PadDO)") (class "Default")
      (node (ref "LED32") (pin "DO") (pinfunction "DO_DO") (pintype "output"))
      (node (ref "LED33") (pin "DI") (pinfunction "DI_DI") (pintype "input"))
    )
    (net (code "37") (name "Net-(LED33-PadDO)") (class "Default")
      (node (ref "LED33") (pin "DO") (pinfunction "DO_DO") (pintype "output"))
      (node (ref "LED34") (pin "DI") (pinfunction "DI_DI") (pintype "input"))
    )
    (net (code "38") (name "Net-(LED34-PadDO)") (class "Default")
      (node (ref "LED34") (pin "DO") (pinfunction "DO_DO") (pintype "output"))
      (node (ref "LED35") (pin "DI") (pinfunction "DI_DI") (pintype "input"))
    )
    (net (code "39") (name "Net-(LED35-PadDO)") (class "Default")
      (node (ref "LED35") (pin "DO") (pinfunction "DO_DO") (pintype "output"))
      (node (ref "LED36") (pin "DI") (pinfunction "DI_DI") (pintype "input"))
    )
    (net (code "40") (name "Net-(LED36-PadDO)") (class "Default")
      (node (ref "LED36") (pin "DO") (pinfunction "DO_DO") (pintype "output"))
      (node (ref "LED37") (pin "DI") (pinfunction "DI_DI") (pintype "input"))
    )
    (net (code "41") (name "Net-(LED37-PadDO)") (class "Default")
      (node (ref "LED37") (pin "DO") (pinfunction "DO_DO") (pintype "output"))
      (node (ref "LED38") (pin "DI") (pinfunction "DI_DI") (pintype "input"))
    )
    (net (code "42") (name "Net-(LED38-PadDO)") (class "Default")
      (node (ref "LED38") (pin "DO") (pinfunction "DO_DO") (pintype "output"))
      (node (ref "LED39") (pin "DI") (pinfunction "DI_DI") (pintype "input"))
    )
    (net (code "43") (name "Net-(LED39-PadDO)") (class "Default")
      (node (ref "LED39") (pin "DO") (pinfunction "DO_DO") (pintype "output"))
      (node (ref "LED40") (pin "DI") (pinfunction "DI_DI") (pintype "input"))
    )
  )
)
